# Connector_FPC_V2025_12.net
KiCad netlist of a schematic drawn in EasyEDA Pro
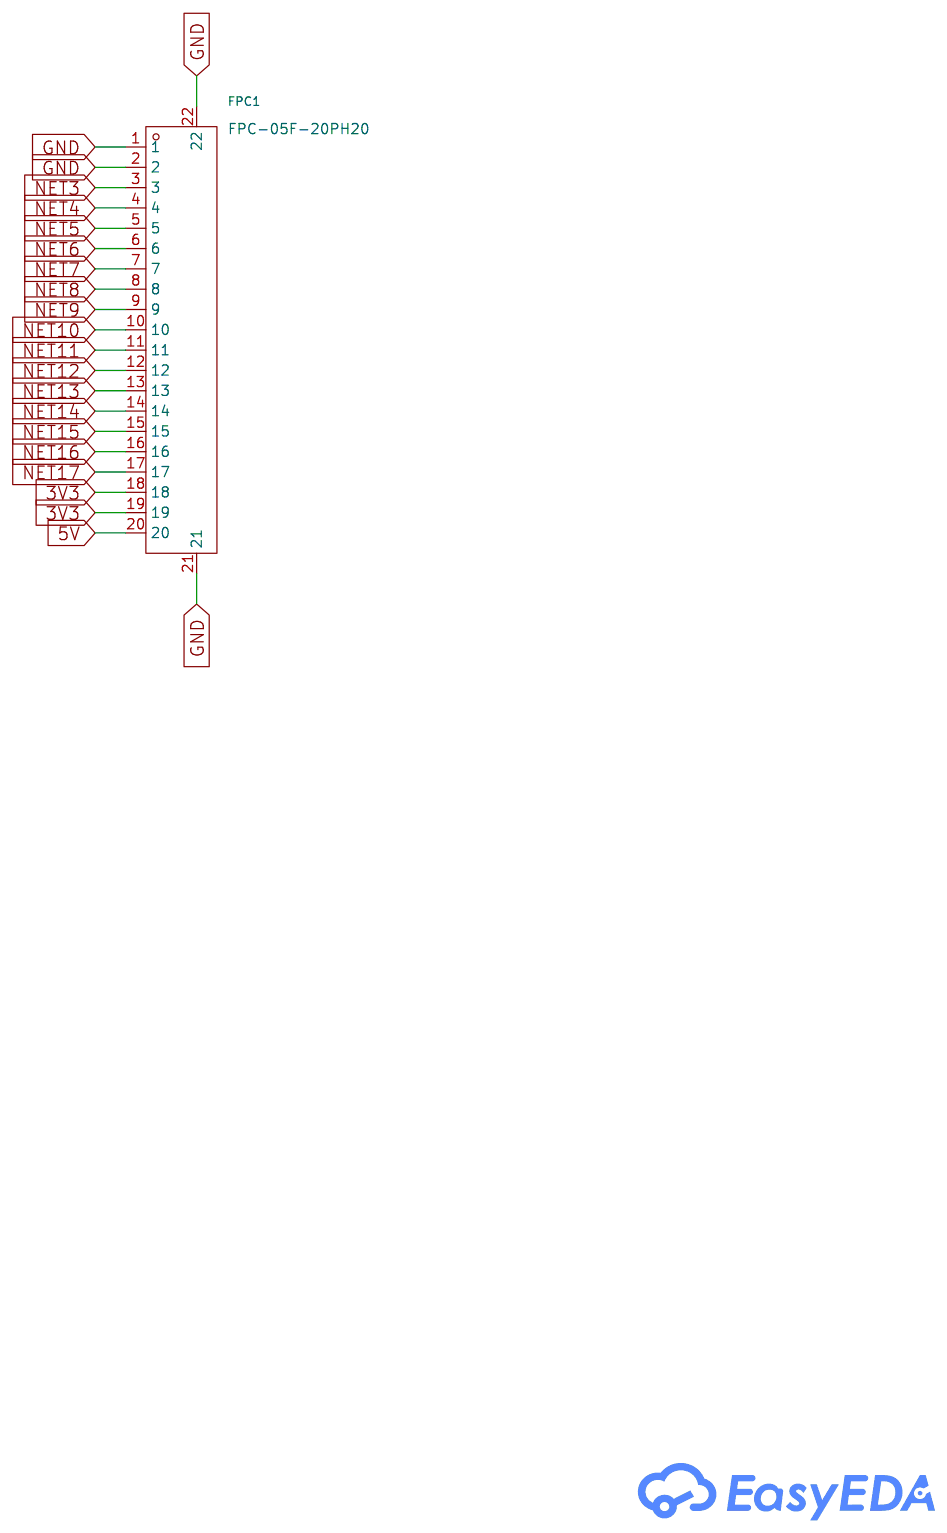
[diagram p0: schematic sheet]

(export (version "E")
  (design (tool "Eeschema 10.0.6"))
  (components
    (comp (ref "FPC1")
      (value "FPC-05F-20PH20")
      (footprint "easyedapro:FPC-SMD_20P-P0.50_XUNPU_FPC-05F-20PH20")
      (fields (field (name "Manufacturer") "XUNPU(讯普)"))
      (libsource (lib "easyedapro") (part "FPC-05F-20PH20"))
    )
  )
  (nets
    (net (code "1") (name "3V3") (class "Default")
      (node (ref "FPC1") (pin "18") (pinfunction "18_18") (pintype "input"))
      (node (ref "FPC1") (pin "19") (pinfunction "19_19") (pintype "input"))
    )
    (net (code "2") (name "5V") (class "Default")
      (node (ref "FPC1") (pin "20") (pinfunction "20_20") (pintype "input"))
    )
    (net (code "3") (name "GND") (class "Default")
      (node (ref "FPC1") (pin "1") (pinfunction "1_1") (pintype "input"))
      (node (ref "FPC1") (pin "2") (pinfunction "2_2") (pintype "input"))
      (node (ref "FPC1") (pin "21") (pinfunction "21_21") (pintype "input"))
      (node (ref "FPC1") (pin "22") (pinfunction "22_22") (pintype "input"))
    )
    (net (code "4") (name "NET3") (class "Default")
      (node (ref "FPC1") (pin "3") (pinfunction "3_3") (pintype "input"))
    )
    (net (code "5") (name "NET4") (class "Default")
      (node (ref "FPC1") (pin "4") (pinfunction "4_4") (pintype "input"))
    )
    (net (code "6") (name "NET5") (class "Default")
      (node (ref "FPC1") (pin "5") (pinfunction "5_5") (pintype "input"))
    )
    (net (code "7") (name "NET6") (class "Default")
      (node (ref "FPC1") (pin "6") (pinfunction "6_6") (pintype "input"))
    )
    (net (code "8") (name "NET7") (class "Default")
      (node (ref "FPC1") (pin "7") (pinfunction "7_7") (pintype "input"))
    )
    (net (code "9") (name "NET8") (class "Default")
      (node (ref "FPC1") (pin "8") (pinfunction "8_8") (pintype "input"))
    )
    (net (code "10") (name "NET9") (class "Default")
      (node (ref "FPC1") (pin "9") (pinfunction "9_9") (pintype "input"))
    )
    (net (code "11") (name "NET10") (class "Default")
      (node (ref "FPC1") (pin "10") (pinfunction "10_10") (pintype "input"))
    )
    (net (code "12") (name "NET11") (class "Default")
      (node (ref "FPC1") (pin "11") (pinfunction "11_11") (pintype "input"))
    )
    (net (code "13") (name "NET12") (class "Default")
      (node (ref "FPC1") (pin "12") (pinfunction "12_12") (pintype "input"))
    )
    (net (code "14") (name "NET13") (class "Default")
      (node (ref "FPC1") (pin "13") (pinfunction "13_13") (pintype "input"))
    )
    (net (code "15") (name "NET14") (class "Default")
      (node (ref "FPC1") (pin "14") (pinfunction "14_14") (pintype "input"))
    )
    (net (code "16") (name "NET15") (class "Default")
      (node (ref "FPC1") (pin "15") (pinfunction "15_15") (pintype "input"))
    )
    (net (code "17") (name "NET16") (class "Default")
      (node (ref "FPC1") (pin "16") (pinfunction "16_16") (pintype "input"))
    )
    (net (code "18") (name "NET17") (class "Default")
      (node (ref "FPC1") (pin "17") (pinfunction "17_17") (pintype "input"))
    )
  )
)
